# RS485.net
KiCad netlist of a schematic drawn in Altium Designer
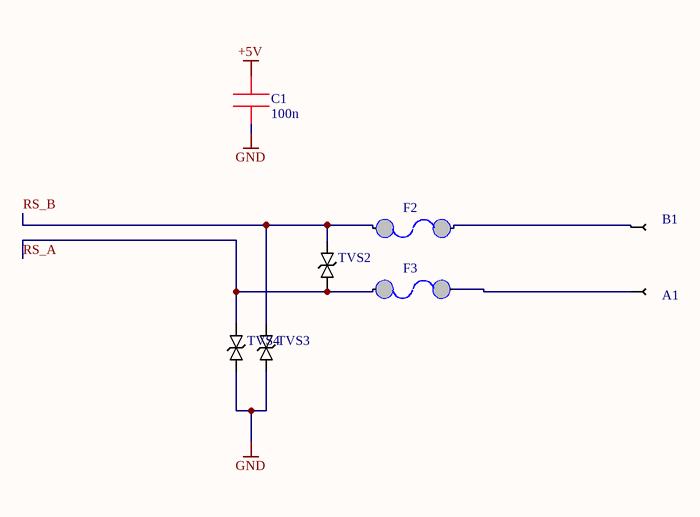
[diagram p0: RS485.SchDoc]

(export (version "E")
  (design (tool "Eeschema 10.0.6"))
  (components
    (comp (ref "A1")
      (value "PIN_Wire")
      (footprint "PIN_wire")
      (description "pin")
      (libsource (lib "kontr") (part "PIN_Wire"))
    )
    (comp (ref "B1")
      (value "PIN_Wire")
      (footprint "PIN_wire")
      (description "pin")
      (libsource (lib "kontr") (part "PIN_Wire"))
    )
    (comp (ref "C1")
      (value "100n")
      (footprint "0402")
      (description "C1005X7R1H104K050BB")
      (libsource (lib "kontr") (part "0805 Cap"))
    )
    (comp (ref "F2")
      (value "Fuse PTS")
      (footprint "Fuse USMF005")
      (description "MF-USMF005-2")
      (libsource (lib "kontr") (part "Fuse PTS"))
    )
    (comp (ref "F3")
      (value "Fuse PTS")
      (footprint "Fuse USMF005")
      (description "MF-USMF005-2")
      (libsource (lib "kontr") (part "Fuse PTS"))
    )
    (comp (ref "TVS2")
      (value "SMAJ5.0CA")
      (footprint "DO-214AC")
      (description "SMAJ30CA")
      (libsource (lib "kontr") (part "SMAJ5.0CA"))
    )
    (comp (ref "TVS3")
      (value "SMAJ5.0CA")
      (footprint "DO-214AC")
      (description "SMAJ30CA")
      (libsource (lib "kontr") (part "SMAJ5.0CA"))
    )
    (comp (ref "TVS4")
      (value "SMAJ5.0CA")
      (footprint "DO-214AC")
      (description "SMAJ30CA")
      (libsource (lib "kontr") (part "SMAJ5.0CA"))
    )
  )
  (nets
    (net (code "1") (name "+5V") (class "Default")
      (node (ref "C1") (pin "2") (pinfunction "2_2") (pintype "passive"))
    )
    (net (code "2") (name "/RS_A") (class "Default")
      (node (ref "F3") (pin "0") (pinfunction "0_0") (pintype "passive"))
      (node (ref "TVS2") (pin "1") (pinfunction "1_1") (pintype "passive"))
      (node (ref "TVS4") (pin "2") (pinfunction "2_2") (pintype "passive"))
    )
    (net (code "3") (name "/RS_B") (class "Default")
      (node (ref "F2") (pin "0") (pinfunction "0_0") (pintype "passive"))
      (node (ref "TVS2") (pin "2") (pinfunction "2_2") (pintype "passive"))
      (node (ref "TVS3") (pin "2") (pinfunction "2_2") (pintype "passive"))
    )
    (net (code "4") (name "GND") (class "Default")
      (node (ref "C1") (pin "1") (pinfunction "1_1") (pintype "passive"))
      (node (ref "TVS3") (pin "1") (pinfunction "1_1") (pintype "passive"))
      (node (ref "TVS4") (pin "1") (pinfunction "1_1") (pintype "passive"))
    )
    (net (code "5") (name "Net-(A1-Pad0)") (class "Default")
      (node (ref "A1") (pin "0") (pinfunction "0_0") (pintype "passive"))
      (node (ref "F3") (pin "1") (pinfunction "1_1") (pintype "passive"))
    )
    (net (code "6") (name "Net-(B1-Pad0)") (class "Default")
      (node (ref "B1") (pin "0") (pinfunction "0_0") (pintype "passive"))
      (node (ref "F2") (pin "1") (pinfunction "1_1") (pintype "passive"))
    )
  )
)
